# Transceiver.net
KiCad netlist of a schematic drawn in Altium Designer
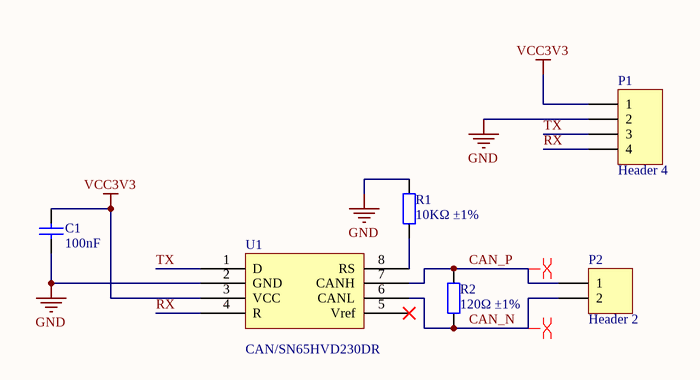
[diagram p0: Transceiver.SchDoc]

(export (version "E")
  (design (tool "Eeschema 10.0.6"))
  (components
    (comp (ref "C1")
      (value "100nF")
      (footprint "0402_C")
      (description "Chip capacitors")
      (fields
        (field (name "MANUFACTURER") "Samsung Electro-Mechanics")
        (field (name "PARTNUMBER") "CL05B104KO5NNNC")
      )
      (libsource (lib "Miscellaneous Devices LC") (part "0402 100nF (104) 10% 16V"))
    )
    (comp (ref "P1")
      (value "Header 4")
      (footprint "HDR1X4")
      (description "Header, 4-Pin")
      (fields (field (name "PUBLISHER") "Altium Limited"))
      (libsource (lib "Miscellaneous Connectors") (part "Header 4"))
    )
    (comp (ref "P2")
      (value "Header 2")
      (footprint "HDR1X2")
      (description "Header, 2-Pin")
      (fields (field (name "PUBLISHER") "Altium Limited"))
      (libsource (lib "Miscellaneous Connectors") (part "Header 2"))
    )
    (comp (ref "R1")
      (value "10KΩ ±1%")
      (footprint "0402_R")
      (description "Chip resistor")
      (fields (field (name "MANUFACTURER") "Uniroyal Elec") (field (name "PARTNUMBER") "0402WGF1002TCE"))
      (libsource (lib "Miscellaneous Devices LC") (part "0402 10K (1002) 1%"))
    )
    (comp (ref "R2")
      (value "120Ω ±1%")
      (footprint "0402_R")
      (description "Chip resistor")
      (fields (field (name "MANUFACTURER") "Uniroyal Elec") (field (name "PARTNUMBER") "0402WGF1200TCE"))
      (libsource (lib "Miscellaneous Devices LC") (part "0402 120R (1200) 1%"))
    )
    (comp (ref "U1")
      (value "CAN/SN65HVD230DR")
      (footprint "SOIC-8_150mil")
      (description "CAN")
      (libsource (lib "Miscellaneous Devices LC") (part "CAN/SN65HVD230DR_[C12084]"))
    )
  )
  (nets
    (net (code "1") (name "/CAN_N") (class "Default")
      (node (ref "P2") (pin "2") (pinfunction "2_2") (pintype "passive"))
      (node (ref "R2") (pin "1") (pinfunction "1_1") (pintype "passive"))
      (node (ref "U1") (pin "6") (pinfunction "CANL_6") (pintype "passive"))
    )
    (net (code "2") (name "/CAN_P") (class "Default")
      (node (ref "P2") (pin "1") (pinfunction "1_1") (pintype "passive"))
      (node (ref "R2") (pin "2") (pinfunction "2_2") (pintype "passive"))
      (node (ref "U1") (pin "7") (pinfunction "CANH_7") (pintype "passive"))
    )
    (net (code "3") (name "/RX") (class "Default")
      (node (ref "P1") (pin "4") (pinfunction "4_4") (pintype "passive"))
      (node (ref "U1") (pin "4") (pinfunction "R_4") (pintype "passive"))
    )
    (net (code "4") (name "/TX") (class "Default")
      (node (ref "P1") (pin "3") (pinfunction "3_3") (pintype "passive"))
      (node (ref "U1") (pin "1") (pinfunction "D_1") (pintype "passive"))
    )
    (net (code "5") (name "GND") (class "Default")
      (node (ref "C1") (pin "1") (pinfunction "1_1") (pintype "passive"))
      (node (ref "P1") (pin "2") (pinfunction "2_2") (pintype "passive"))
      (node (ref "R1") (pin "2") (pinfunction "2_2") (pintype "passive"))
      (node (ref "U1") (pin "2") (pinfunction "GND_2") (pintype "passive"))
    )
    (net (code "6") (name "Net-(U1-RS)") (class "Default")
      (node (ref "R1") (pin "1") (pinfunction "1_1") (pintype "passive"))
      (node (ref "U1") (pin "8") (pinfunction "RS_8") (pintype "passive"))
    )
    (net (code "7") (name "VCC3V3") (class "Default")
      (node (ref "C1") (pin "2") (pinfunction "2_2") (pintype "passive"))
      (node (ref "P1") (pin "1") (pinfunction "1_1") (pintype "passive"))
      (node (ref "U1") (pin "3") (pinfunction "VCC_3") (pintype "passive"))
    )
    (net (code "8") (name "unconnected-(U1-Vref-Pad5)") (class "Default")
      (node (ref "U1") (pin "5") (pinfunction "Vref_5") (pintype "passive+no_connect"))
    )
  )
)
